# W5100_ethernet_shield.net
KiCad netlist of a schematic drawn in EAGLE
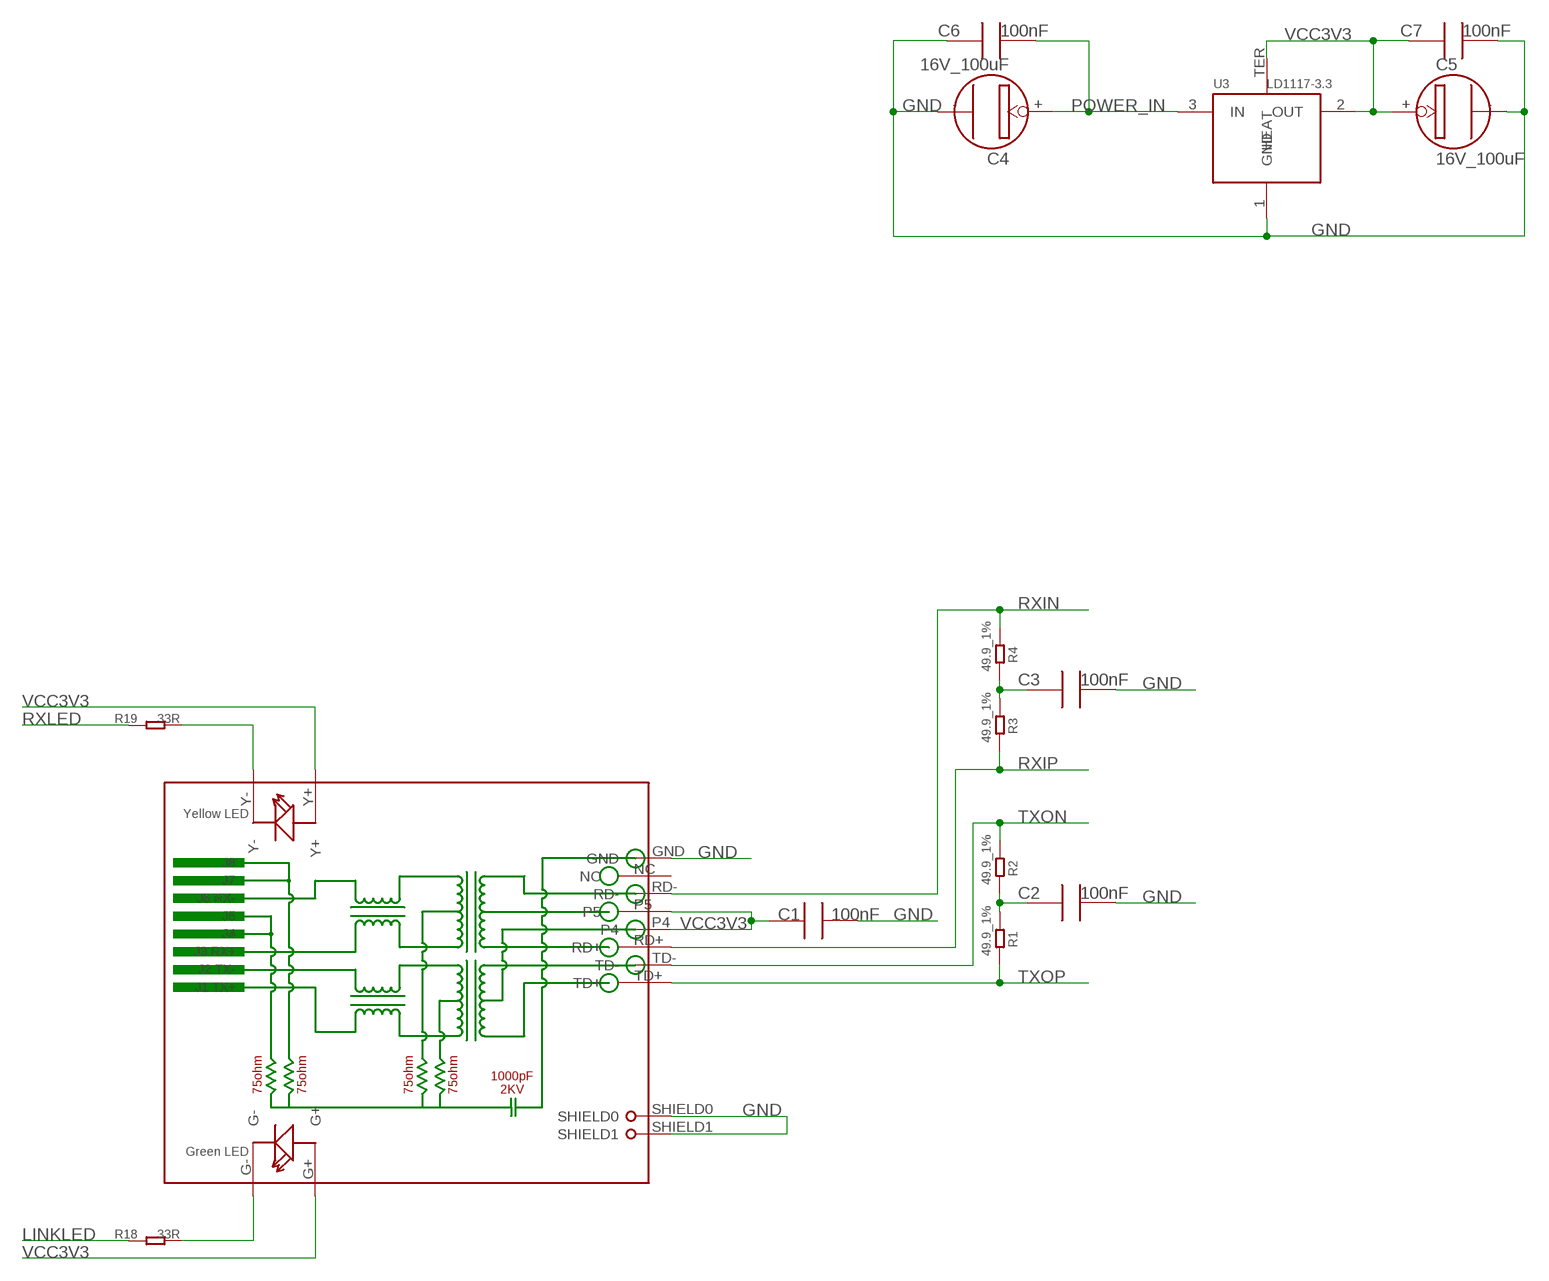
[diagram p0: schematic, sheet 1, part 1 of 2]
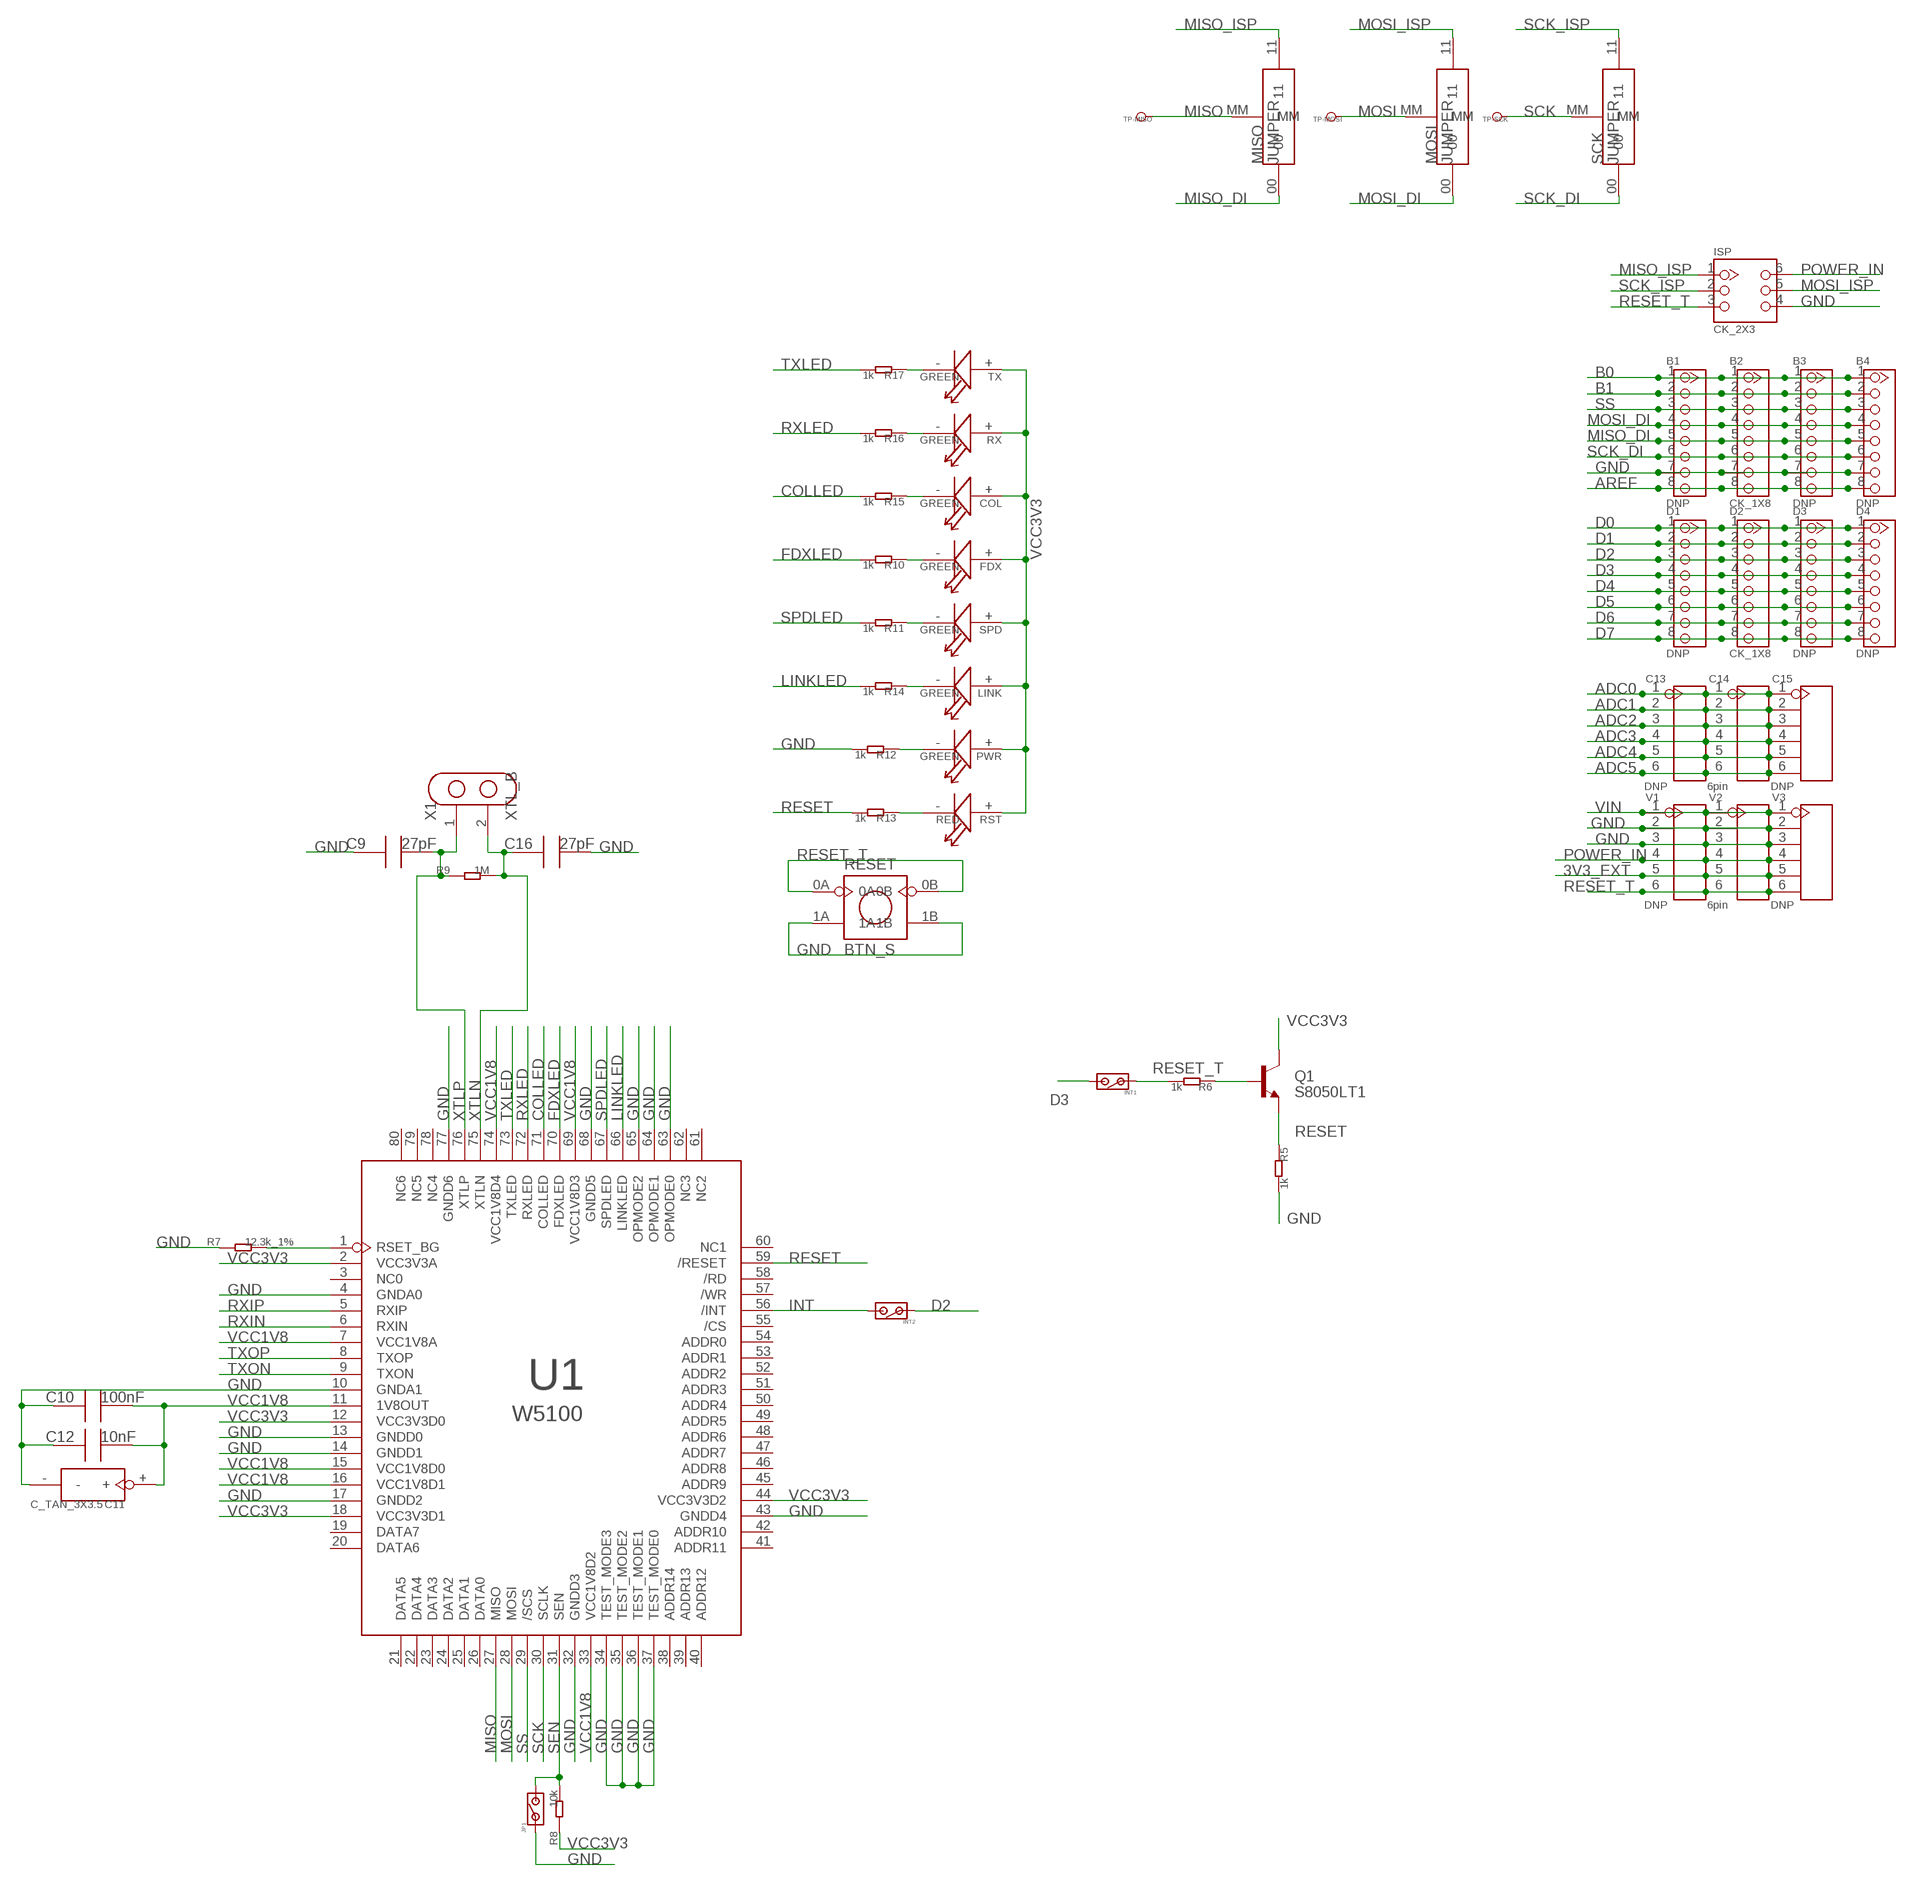
[diagram p1: schematic, sheet 1, part 2 of 2]

(export (version "E")
  (design (tool "Eeschema 10.0.6"))
  (components
    (comp (ref "B1")
      (value "DNP")
      (footprint "eagle-import:CK_1X8")
      (libsource (lib "eagle-import") (part "CK_1X8DD"))
    )
    (comp (ref "B2")
      (value "CK_1X8")
      (footprint "eagle-import:CK_1X8")
      (libsource (lib "eagle-import") (part "CK_1X8DD"))
    )
    (comp (ref "B3")
      (value "DNP")
      (footprint "eagle-import:CK_1X8")
      (libsource (lib "eagle-import") (part "CK_1X8DD"))
    )
    (comp (ref "B4")
      (value "DNP")
      (footprint "eagle-import:CK_1X8")
      (libsource (lib "eagle-import") (part "CK_1X8DD"))
    )
    (comp (ref "C1")
      (value "100nF")
      (footprint "eagle-import:0603")
      (libsource (lib "eagle-import") (part "C0603"))
    )
    (comp (ref "C2")
      (value "100nF")
      (footprint "eagle-import:0603")
      (libsource (lib "eagle-import") (part "C0603"))
    )
    (comp (ref "C3")
      (value "100nF")
      (footprint "eagle-import:0603")
      (libsource (lib "eagle-import") (part "C0603"))
    )
    (comp (ref "C4")
      (value "16V_100uF")
      (footprint "eagle-import:SANYO-OSCON_SMD_C6")
      (libsource (lib "eagle-import") (part "PANASONIC_D260"))
    )
    (comp (ref "C5")
      (value "16V_100uF")
      (footprint "eagle-import:SANYO-OSCON_SMD_C6")
      (libsource (lib "eagle-import") (part "PANASONIC_D260"))
    )
    (comp (ref "C6")
      (value "100nF")
      (footprint "eagle-import:0603")
      (libsource (lib "eagle-import") (part "C0603"))
    )
    (comp (ref "C7")
      (value "100nF")
      (footprint "eagle-import:0603")
      (libsource (lib "eagle-import") (part "C0603"))
    )
    (comp (ref "C9")
      (value "27pF")
      (footprint "eagle-import:0603")
      (libsource (lib "eagle-import") (part "C0603"))
    )
    (comp (ref "C10")
      (value "100nF")
      (footprint "eagle-import:0603")
      (libsource (lib "eagle-import") (part "C0603"))
    )
    (comp (ref "C11")
      (value "C_TAN_3X3.5")
      (footprint "eagle-import:C_TAN_3X3.5")
      (libsource (lib "eagle-import") (part "C_TAN_3X3.5"))
    )
    (comp (ref "C12")
      (value "10nF")
      (footprint "eagle-import:0603")
      (libsource (lib "eagle-import") (part "C0603"))
    )
    (comp (ref "C13")
      (value "DNP")
      (footprint "eagle-import:CK_1_6")
      (libsource (lib "eagle-import") (part "CK_16"))
    )
    (comp (ref "C14")
      (value "6pin")
      (footprint "eagle-import:CK_1_6")
      (libsource (lib "eagle-import") (part "CK_16"))
    )
    (comp (ref "C15")
      (value "DNP")
      (footprint "eagle-import:CK_1_6")
      (libsource (lib "eagle-import") (part "CK_16"))
    )
    (comp (ref "C16")
      (value "27pF")
      (footprint "eagle-import:0603")
      (libsource (lib "eagle-import") (part "C0603"))
    )
    (comp (ref "COL")
      (value "GREEN")
      (footprint "eagle-import:LED0805")
      (libsource (lib "eagle-import") (part "LED0805"))
    )
    (comp (ref "D1")
      (value "DNP")
      (footprint "eagle-import:CK_1X8")
      (libsource (lib "eagle-import") (part "CK_1X8DD"))
    )
    (comp (ref "D2")
      (value "CK_1X8")
      (footprint "eagle-import:CK_1X8")
      (libsource (lib "eagle-import") (part "CK_1X8DD"))
    )
    (comp (ref "D3")
      (value "DNP")
      (footprint "eagle-import:CK_1X8")
      (libsource (lib "eagle-import") (part "CK_1X8DD"))
    )
    (comp (ref "D4")
      (value "DNP")
      (footprint "eagle-import:CK_1X8")
      (libsource (lib "eagle-import") (part "CK_1X8DD"))
    )
    (comp (ref "FDX")
      (value "GREEN")
      (footprint "eagle-import:LED0805")
      (libsource (lib "eagle-import") (part "LED0805"))
    )
    (comp (ref "INT1")
      (value "DNP")
      (footprint "eagle-import:JP_SW")
      (libsource (lib "eagle-import") (part "JP_SW"))
    )
    (comp (ref "INT2")
      (value "DNP")
      (footprint "eagle-import:JP_SW")
      (libsource (lib "eagle-import") (part "JP_SW"))
    )
    (comp (ref "ISP")
      (value "CK_2X3")
      (footprint "eagle-import:CK_2X3_THIN")
      (libsource (lib "eagle-import") (part "CK_2X3"))
    )
    (comp (ref "JP1")
      (value "DNP")
      (footprint "eagle-import:JP_SW")
      (libsource (lib "eagle-import") (part "JP_SW"))
    )
    (comp (ref "LINK")
      (value "GREEN")
      (footprint "eagle-import:LED0805")
      (libsource (lib "eagle-import") (part "LED0805"))
    )
    (comp (ref "MISO")
      (value "JUMPER")
      (footprint "eagle-import:JUMPER")
      (libsource (lib "eagle-import") (part "JUMPER"))
    )
    (comp (ref "MOSI")
      (value "JUMPER")
      (footprint "eagle-import:JUMPER")
      (libsource (lib "eagle-import") (part "JUMPER"))
    )
    (comp (ref "PWR")
      (value "GREEN")
      (footprint "eagle-import:LED0805")
      (libsource (lib "eagle-import") (part "LED0805"))
    )
    (comp (ref "Q1")
      (value "S8050LT1")
      (footprint "eagle-import:SOT23")
      (libsource (lib "eagle-import") (part "TRANSISTOR_NPNSOT23"))
    )
    (comp (ref "R1")
      (value "49.9_1%")
      (footprint "eagle-import:0603")
      (libsource (lib "eagle-import") (part "R0603"))
    )
    (comp (ref "R2")
      (value "49.9_1%")
      (footprint "eagle-import:0603")
      (libsource (lib "eagle-import") (part "R0603"))
    )
    (comp (ref "R3")
      (value "49.9_1%")
      (footprint "eagle-import:0603")
      (libsource (lib "eagle-import") (part "R0603"))
    )
    (comp (ref "R4")
      (value "49.9_1%")
      (footprint "eagle-import:0603")
      (libsource (lib "eagle-import") (part "R0603"))
    )
    (comp (ref "R5")
      (value "1k")
      (footprint "eagle-import:0603")
      (libsource (lib "eagle-import") (part "R0603"))
    )
    (comp (ref "R6")
      (value "1k")
      (footprint "eagle-import:0603")
      (libsource (lib "eagle-import") (part "R0603"))
    )
    (comp (ref "R7")
      (value "12.3k_1%")
      (footprint "eagle-import:0603")
      (libsource (lib "eagle-import") (part "R0603"))
    )
    (comp (ref "R8")
      (value "10k")
      (footprint "eagle-import:0603")
      (libsource (lib "eagle-import") (part "R0603"))
    )
    (comp (ref "R9")
      (value "1M")
      (footprint "eagle-import:0603")
      (libsource (lib "eagle-import") (part "R0603"))
    )
    (comp (ref "R10")
      (value "1k")
      (footprint "eagle-import:0603")
      (libsource (lib "eagle-import") (part "R0603"))
    )
    (comp (ref "R11")
      (value "1k")
      (footprint "eagle-import:0603")
      (libsource (lib "eagle-import") (part "R0603"))
    )
    (comp (ref "R12")
      (value "1k")
      (footprint "eagle-import:0603")
      (libsource (lib "eagle-import") (part "R0603"))
    )
    (comp (ref "R13")
      (value "1k")
      (footprint "eagle-import:0603")
      (libsource (lib "eagle-import") (part "R0603"))
    )
    (comp (ref "R14")
      (value "1k")
      (footprint "eagle-import:0603")
      (libsource (lib "eagle-import") (part "R0603"))
    )
    (comp (ref "R15")
      (value "1k")
      (footprint "eagle-import:0603")
      (libsource (lib "eagle-import") (part "R0603"))
    )
    (comp (ref "R16")
      (value "1k")
      (footprint "eagle-import:0603")
      (libsource (lib "eagle-import") (part "R0603"))
    )
    (comp (ref "R17")
      (value "1k")
      (footprint "eagle-import:0603")
      (libsource (lib "eagle-import") (part "R0603"))
    )
    (comp (ref "R18")
      (value "33R")
      (footprint "eagle-import:0603")
      (libsource (lib "eagle-import") (part "R0603"))
    )
    (comp (ref "R19")
      (value "33R")
      (footprint "eagle-import:0603")
      (libsource (lib "eagle-import") (part "R0603"))
    )
    (comp (ref "RESET")
      (value "BTN_S")
      (footprint "eagle-import:BTN_S")
      (libsource (lib "eagle-import") (part "BTN_S"))
    )
    (comp (ref "RJ1")
      (value "HR911105A")
      (footprint "eagle-import:HR911105A")
      (libsource (lib "eagle-import") (part "HR911105A"))
    )
    (comp (ref "RST")
      (value "RED")
      (footprint "eagle-import:LED0805")
      (libsource (lib "eagle-import") (part "LED0805"))
    )
    (comp (ref "RX")
      (value "GREEN")
      (footprint "eagle-import:LED0805")
      (libsource (lib "eagle-import") (part "LED0805"))
    )
    (comp (ref "SCK")
      (value "JUMPER")
      (footprint "eagle-import:JUMPER")
      (libsource (lib "eagle-import") (part "JUMPER"))
    )
    (comp (ref "SPD")
      (value "GREEN")
      (footprint "eagle-import:LED0805")
      (libsource (lib "eagle-import") (part "LED0805"))
    )
    (comp (ref "TP-MISO")
      (value "DNP")
      (footprint "eagle-import:TP_45X45")
      (libsource (lib "eagle-import") (part "PAD-TEST-POINT-CIRCLE'45X45'"))
    )
    (comp (ref "TP-MOSI")
      (value "DNP")
      (footprint "eagle-import:TP_45X45")
      (libsource (lib "eagle-import") (part "PAD-TEST-POINT-CIRCLE'45X45'"))
    )
    (comp (ref "TP-SCK")
      (value "DNP")
      (footprint "eagle-import:TP_45X45")
      (libsource (lib "eagle-import") (part "PAD-TEST-POINT-CIRCLE'45X45'"))
    )
    (comp (ref "TX")
      (value "GREEN")
      (footprint "eagle-import:LED0805")
      (libsource (lib "eagle-import") (part "LED0805"))
    )
    (comp (ref "U1")
      (value "W5100")
      (footprint "eagle-import:SQFP80")
      (libsource (lib "eagle-import") (part "W5100"))
    )
    (comp (ref "U3")
      (value "LD1117-3.3")
      (footprint "eagle-import:SOT223")
      (libsource (lib "eagle-import") (part "LD1117SOT223"))
    )
    (comp (ref "V1")
      (value "DNP")
      (footprint "eagle-import:CK_1_6")
      (libsource (lib "eagle-import") (part "CK_16"))
    )
    (comp (ref "V2")
      (value "6pin")
      (footprint "eagle-import:CK_1_6")
      (libsource (lib "eagle-import") (part "CK_16"))
    )
    (comp (ref "V3")
      (value "DNP")
      (footprint "eagle-import:CK_1_6")
      (libsource (lib "eagle-import") (part "CK_16"))
    )
    (comp (ref "X1")
      (value "XTL_B")
      (footprint "eagle-import:XTL_B")
      (libsource (lib "eagle-import") (part "XTL_B"))
    )
  )
  (nets
    (net (code "1") (name "/3V3_EXT") (class "Default")
      (node (ref "V1") (pin "5") (pinfunction "5_5") (pintype "bidirectional"))
      (node (ref "V2") (pin "5") (pinfunction "5_5") (pintype "bidirectional"))
      (node (ref "V3") (pin "5") (pinfunction "5_5") (pintype "bidirectional"))
    )
    (net (code "2") (name "/ADC0") (class "Default")
      (node (ref "C13") (pin "1") (pinfunction "1_1") (pintype "bidirectional"))
      (node (ref "C14") (pin "1") (pinfunction "1_1") (pintype "bidirectional"))
      (node (ref "C15") (pin "1") (pinfunction "1_1") (pintype "bidirectional"))
    )
    (net (code "3") (name "/ADC1") (class "Default")
      (node (ref "C13") (pin "2") (pinfunction "2_2") (pintype "bidirectional"))
      (node (ref "C14") (pin "2") (pinfunction "2_2") (pintype "bidirectional"))
      (node (ref "C15") (pin "2") (pinfunction "2_2") (pintype "bidirectional"))
    )
    (net (code "4") (name "/ADC2") (class "Default")
      (node (ref "C13") (pin "3") (pinfunction "3_3") (pintype "bidirectional"))
      (node (ref "C14") (pin "3") (pinfunction "3_3") (pintype "bidirectional"))
      (node (ref "C15") (pin "3") (pinfunction "3_3") (pintype "bidirectional"))
    )
    (net (code "5") (name "/ADC3") (class "Default")
      (node (ref "C13") (pin "4") (pinfunction "4_4") (pintype "bidirectional"))
      (node (ref "C14") (pin "4") (pinfunction "4_4") (pintype "bidirectional"))
      (node (ref "C15") (pin "4") (pinfunction "4_4") (pintype "bidirectional"))
    )
    (net (code "6") (name "/ADC4") (class "Default")
      (node (ref "C13") (pin "5") (pinfunction "5_5") (pintype "bidirectional"))
      (node (ref "C14") (pin "5") (pinfunction "5_5") (pintype "bidirectional"))
      (node (ref "C15") (pin "5") (pinfunction "5_5") (pintype "bidirectional"))
    )
    (net (code "7") (name "/ADC5") (class "Default")
      (node (ref "C13") (pin "6") (pinfunction "6_6") (pintype "bidirectional"))
      (node (ref "C14") (pin "6") (pinfunction "6_6") (pintype "bidirectional"))
      (node (ref "C15") (pin "6") (pinfunction "6_6") (pintype "bidirectional"))
    )
    (net (code "8") (name "/AREF") (class "Default")
      (node (ref "B1") (pin "8") (pinfunction "P$8_8") (pintype "bidirectional"))
      (node (ref "B2") (pin "8") (pinfunction "P$8_8") (pintype "bidirectional"))
      (node (ref "B3") (pin "8") (pinfunction "P$8_8") (pintype "bidirectional"))
      (node (ref "B4") (pin "8") (pinfunction "P$8_8") (pintype "bidirectional"))
    )
    (net (code "9") (name "/B0") (class "Default")
      (node (ref "B1") (pin "1") (pinfunction "P$1_1") (pintype "bidirectional"))
      (node (ref "B2") (pin "1") (pinfunction "P$1_1") (pintype "bidirectional"))
      (node (ref "B3") (pin "1") (pinfunction "P$1_1") (pintype "bidirectional"))
      (node (ref "B4") (pin "1") (pinfunction "P$1_1") (pintype "bidirectional"))
    )
    (net (code "10") (name "/B1") (class "Default")
      (node (ref "B1") (pin "2") (pinfunction "P$2_2") (pintype "bidirectional"))
      (node (ref "B2") (pin "2") (pinfunction "P$2_2") (pintype "bidirectional"))
      (node (ref "B3") (pin "2") (pinfunction "P$2_2") (pintype "bidirectional"))
      (node (ref "B4") (pin "2") (pinfunction "P$2_2") (pintype "bidirectional"))
    )
    (net (code "11") (name "/COLLED") (class "Default")
      (node (ref "R15") (pin "2") (pinfunction "2_2") (pintype "bidirectional"))
      (node (ref "U1") (pin "71") (pinfunction "COLLED_71") (pintype "bidirectional"))
    )
    (net (code "12") (name "/D0") (class "Default")
      (node (ref "D1") (pin "1") (pinfunction "P$1_1") (pintype "bidirectional"))
      (node (ref "D2") (pin "1") (pinfunction "P$1_1") (pintype "bidirectional"))
      (node (ref "D3") (pin "1") (pinfunction "P$1_1") (pintype "bidirectional"))
      (node (ref "D4") (pin "1") (pinfunction "P$1_1") (pintype "bidirectional"))
    )
    (net (code "13") (name "/D1") (class "Default")
      (node (ref "D1") (pin "2") (pinfunction "P$2_2") (pintype "bidirectional"))
      (node (ref "D2") (pin "2") (pinfunction "P$2_2") (pintype "bidirectional"))
      (node (ref "D3") (pin "2") (pinfunction "P$2_2") (pintype "bidirectional"))
      (node (ref "D4") (pin "2") (pinfunction "P$2_2") (pintype "bidirectional"))
    )
    (net (code "14") (name "/D2") (class "Default")
      (node (ref "D1") (pin "3") (pinfunction "P$3_3") (pintype "bidirectional"))
      (node (ref "D2") (pin "3") (pinfunction "P$3_3") (pintype "bidirectional"))
      (node (ref "D3") (pin "3") (pinfunction "P$3_3") (pintype "bidirectional"))
      (node (ref "D4") (pin "3") (pinfunction "P$3_3") (pintype "bidirectional"))
      (node (ref "INT2") (pin "1") (pinfunction "1_1") (pintype "bidirectional"))
    )
    (net (code "15") (name "/D3") (class "Default")
      (node (ref "D1") (pin "4") (pinfunction "P$4_4") (pintype "bidirectional"))
      (node (ref "D2") (pin "4") (pinfunction "P$4_4") (pintype "bidirectional"))
      (node (ref "D3") (pin "4") (pinfunction "P$4_4") (pintype "bidirectional"))
      (node (ref "D4") (pin "4") (pinfunction "P$4_4") (pintype "bidirectional"))
      (node (ref "INT1") (pin "2") (pinfunction "2_2") (pintype "bidirectional"))
    )
    (net (code "16") (name "/D4") (class "Default")
      (node (ref "D1") (pin "5") (pinfunction "P$5_5") (pintype "bidirectional"))
      (node (ref "D2") (pin "5") (pinfunction "P$5_5") (pintype "bidirectional"))
      (node (ref "D3") (pin "5") (pinfunction "P$5_5") (pintype "bidirectional"))
      (node (ref "D4") (pin "5") (pinfunction "P$5_5") (pintype "bidirectional"))
    )
    (net (code "17") (name "/D5") (class "Default")
      (node (ref "D1") (pin "6") (pinfunction "P$6_6") (pintype "bidirectional"))
      (node (ref "D2") (pin "6") (pinfunction "P$6_6") (pintype "bidirectional"))
      (node (ref "D3") (pin "6") (pinfunction "P$6_6") (pintype "bidirectional"))
      (node (ref "D4") (pin "6") (pinfunction "P$6_6") (pintype "bidirectional"))
    )
    (net (code "18") (name "/D6") (class "Default")
      (node (ref "D1") (pin "7") (pinfunction "P$7_7") (pintype "bidirectional"))
      (node (ref "D2") (pin "7") (pinfunction "P$7_7") (pintype "bidirectional"))
      (node (ref "D3") (pin "7") (pinfunction "P$7_7") (pintype "bidirectional"))
      (node (ref "D4") (pin "7") (pinfunction "P$7_7") (pintype "bidirectional"))
    )
    (net (code "19") (name "/D7") (class "Default")
      (node (ref "D1") (pin "8") (pinfunction "P$8_8") (pintype "bidirectional"))
      (node (ref "D2") (pin "8") (pinfunction "P$8_8") (pintype "bidirectional"))
      (node (ref "D3") (pin "8") (pinfunction "P$8_8") (pintype "bidirectional"))
      (node (ref "D4") (pin "8") (pinfunction "P$8_8") (pintype "bidirectional"))
    )
    (net (code "20") (name "/FDXLED") (class "Default")
      (node (ref "R10") (pin "2") (pinfunction "2_2") (pintype "bidirectional"))
      (node (ref "U1") (pin "70") (pinfunction "FDXLED_70") (pintype "bidirectional"))
    )
    (net (code "21") (name "/GND") (class "Default")
      (node (ref "B1") (pin "7") (pinfunction "P$7_7") (pintype "bidirectional"))
      (node (ref "B2") (pin "7") (pinfunction "P$7_7") (pintype "bidirectional"))
      (node (ref "B3") (pin "7") (pinfunction "P$7_7") (pintype "bidirectional"))
      (node (ref "B4") (pin "7") (pinfunction "P$7_7") (pintype "bidirectional"))
      (node (ref "C1") (pin "2") (pinfunction "2_2") (pintype "bidirectional"))
      (node (ref "C10") (pin "1") (pinfunction "1_1") (pintype "bidirectional"))
      (node (ref "C11") (pin "-") (pinfunction "-_-") (pintype "bidirectional"))
      (node (ref "C12") (pin "1") (pinfunction "1_1") (pintype "bidirectional"))
      (node (ref "C16") (pin "2") (pinfunction "2_2") (pintype "bidirectional"))
      (node (ref "C2") (pin "2") (pinfunction "2_2") (pintype "bidirectional"))
      (node (ref "C3") (pin "2") (pinfunction "2_2") (pintype "bidirectional"))
      (node (ref "C4") (pin "-") (pinfunction "-_-") (pintype "bidirectional"))
      (node (ref "C5") (pin "-") (pinfunction "-_-") (pintype "bidirectional"))
      (node (ref "C6") (pin "1") (pinfunction "1_1") (pintype "bidirectional"))
      (node (ref "C7") (pin "2") (pinfunction "2_2") (pintype "bidirectional"))
      (node (ref "C9") (pin "1") (pinfunction "1_1") (pintype "bidirectional"))
      (node (ref "ISP") (pin "4") (pinfunction "P$4_4") (pintype "bidirectional"))
      (node (ref "JP1") (pin "1") (pinfunction "1_1") (pintype "bidirectional"))
      (node (ref "R12") (pin "2") (pinfunction "2_2") (pintype "bidirectional"))
      (node (ref "R5") (pin "2") (pinfunction "2_2") (pintype "bidirectional"))
      (node (ref "R7") (pin "1") (pinfunction "1_1") (pintype "bidirectional"))
      (node (ref "RESET") (pin "1A") (pinfunction "1A_1A") (pintype "bidirectional"))
      (node (ref "RESET") (pin "1B") (pinfunction "1B_1B") (pintype "bidirectional"))
      (node (ref "RJ1") (pin "GND") (pinfunction "GND_GND") (pintype "bidirectional"))
      (node (ref "RJ1") (pin "SHIELD0") (pinfunction "SHIELD0_SHIELD0") (pintype "bidirectional"))
      (node (ref "RJ1") (pin "SHIELD1") (pinfunction "SHIELD1_SHIELD1") (pintype "bidirectional"))
      (node (ref "U1") (pin "10") (pinfunction "GNDA1_10") (pintype "bidirectional"))
      (node (ref "U1") (pin "13") (pinfunction "GNDD0_13") (pintype "bidirectional"))
      (node (ref "U1") (pin "14") (pinfunction "GNDD1_14") (pintype "bidirectional"))
      (node (ref "U1") (pin "17") (pinfunction "GNDD2_17") (pintype "bidirectional"))
      (node (ref "U1") (pin "32") (pinfunction "GNDD3_32") (pintype "bidirectional"))
      (node (ref "U1") (pin "34") (pinfunction "TEST_MODE3_34") (pintype "bidirectional"))
      (node (ref "U1") (pin "35") (pinfunction "TEST_MODE2_35") (pintype "bidirectional"))
      (node (ref "U1") (pin "36") (pinfunction "TEST_MODE1_36") (pintype "bidirectional"))
      (node (ref "U1") (pin "37") (pinfunction "TEST_MODE0_37") (pintype "bidirectional"))
      (node (ref "U1") (pin "4") (pinfunction "GNDA0_4") (pintype "bidirectional"))
      (node (ref "U1") (pin "43") (pinfunction "GNDD4_43") (pintype "bidirectional"))
      (node (ref "U1") (pin "63") (pinfunction "OPMODE0_63") (pintype "bidirectional"))
      (node (ref "U1") (pin "64") (pinfunction "OPMODE1_64") (pintype "bidirectional"))
      (node (ref "U1") (pin "65") (pinfunction "OPMODE2_65") (pintype "bidirectional"))
      (node (ref "U1") (pin "68") (pinfunction "GNDD5_68") (pintype "bidirectional"))
      (node (ref "U1") (pin "77") (pinfunction "GNDD6_77") (pintype "bidirectional"))
      (node (ref "U3") (pin "1") (pinfunction "GND_1") (pintype "bidirectional"))
      (node (ref "V1") (pin "2") (pinfunction "2_2") (pintype "bidirectional"))
      (node (ref "V1") (pin "3") (pinfunction "3_3") (pintype "bidirectional"))
      (node (ref "V2") (pin "2") (pinfunction "2_2") (pintype "bidirectional"))
      (node (ref "V2") (pin "3") (pinfunction "3_3") (pintype "bidirectional"))
      (node (ref "V3") (pin "2") (pinfunction "2_2") (pintype "bidirectional"))
      (node (ref "V3") (pin "3") (pinfunction "3_3") (pintype "bidirectional"))
    )
    (net (code "22") (name "/INT") (class "Default")
      (node (ref "INT2") (pin "2") (pinfunction "2_2") (pintype "bidirectional"))
      (node (ref "U1") (pin "56") (pinfunction "/INT_56") (pintype "bidirectional"))
    )
    (net (code "23") (name "/LINKLED") (class "Default")
      (node (ref "R14") (pin "2") (pinfunction "2_2") (pintype "bidirectional"))
      (node (ref "R18") (pin "1") (pinfunction "1_1") (pintype "bidirectional"))
      (node (ref "U1") (pin "66") (pinfunction "LINKLED_66") (pintype "bidirectional"))
    )
    (net (code "24") (name "/MISO") (class "Default")
      (node (ref "MISO") (pin "MM") (pinfunction "MM_MM") (pintype "bidirectional"))
      (node (ref "TP-MISO") (pin "T") (pinfunction "T_T") (pintype "bidirectional"))
      (node (ref "U1") (pin "27") (pinfunction "MISO_27") (pintype "bidirectional"))
    )
    (net (code "25") (name "/MISO_DI") (class "Default")
      (node (ref "B1") (pin "5") (pinfunction "P$5_5") (pintype "bidirectional"))
      (node (ref "B2") (pin "5") (pinfunction "P$5_5") (pintype "bidirectional"))
      (node (ref "B3") (pin "5") (pinfunction "P$5_5") (pintype "bidirectional"))
      (node (ref "B4") (pin "5") (pinfunction "P$5_5") (pintype "bidirectional"))
      (node (ref "MISO") (pin "00") (pinfunction "00_00") (pintype "bidirectional"))
    )
    (net (code "26") (name "/MISO_ISP") (class "Default")
      (node (ref "ISP") (pin "1") (pinfunction "P$1_1") (pintype "bidirectional"))
      (node (ref "MISO") (pin "11") (pinfunction "11_11") (pintype "bidirectional"))
    )
    (net (code "27") (name "/MOSI") (class "Default")
      (node (ref "MOSI") (pin "MM") (pinfunction "MM_MM") (pintype "bidirectional"))
      (node (ref "TP-MOSI") (pin "T") (pinfunction "T_T") (pintype "bidirectional"))
      (node (ref "U1") (pin "28") (pinfunction "MOSI_28") (pintype "bidirectional"))
    )
    (net (code "28") (name "/MOSI_DI") (class "Default")
      (node (ref "B1") (pin "4") (pinfunction "P$4_4") (pintype "bidirectional"))
      (node (ref "B2") (pin "4") (pinfunction "P$4_4") (pintype "bidirectional"))
      (node (ref "B3") (pin "4") (pinfunction "P$4_4") (pintype "bidirectional"))
      (node (ref "B4") (pin "4") (pinfunction "P$4_4") (pintype "bidirectional"))
      (node (ref "MOSI") (pin "00") (pinfunction "00_00") (pintype "bidirectional"))
    )
    (net (code "29") (name "/MOSI_ISP") (class "Default")
      (node (ref "ISP") (pin "5") (pinfunction "P$5_5") (pintype "bidirectional"))
      (node (ref "MOSI") (pin "11") (pinfunction "11_11") (pintype "bidirectional"))
    )
    (net (code "30") (name "/POWER_IN") (class "Default")
      (node (ref "C4") (pin "+") (pinfunction "+_+") (pintype "bidirectional"))
      (node (ref "C6") (pin "2") (pinfunction "2_2") (pintype "bidirectional"))
      (node (ref "ISP") (pin "6") (pinfunction "P$6_6") (pintype "bidirectional"))
      (node (ref "U3") (pin "3") (pinfunction "IN_3") (pintype "bidirectional"))
      (node (ref "V1") (pin "4") (pinfunction "4_4") (pintype "bidirectional"))
      (node (ref "V2") (pin "4") (pinfunction "4_4") (pintype "bidirectional"))
      (node (ref "V3") (pin "4") (pinfunction "4_4") (pintype "bidirectional"))
    )
    (net (code "31") (name "/RESET") (class "Default")
      (node (ref "Q1") (pin "2") (pinfunction "E_2") (pintype "passive"))
      (node (ref "R13") (pin "2") (pinfunction "2_2") (pintype "bidirectional"))
      (node (ref "R5") (pin "1") (pinfunction "1_1") (pintype "bidirectional"))
      (node (ref "U1") (pin "59") (pinfunction "/RESET_59") (pintype "bidirectional"))
    )
    (net (code "32") (name "/RESET_T") (class "Default")
      (node (ref "INT1") (pin "1") (pinfunction "1_1") (pintype "bidirectional"))
      (node (ref "ISP") (pin "3") (pinfunction "P$3_3") (pintype "bidirectional"))
      (node (ref "R6") (pin "2") (pinfunction "2_2") (pintype "bidirectional"))
      (node (ref "RESET") (pin "0A") (pinfunction "0A_0A") (pintype "bidirectional"))
      (node (ref "RESET") (pin "0B") (pinfunction "0B_0B") (pintype "bidirectional"))
      (node (ref "V1") (pin "6") (pinfunction "6_6") (pintype "bidirectional"))
      (node (ref "V2") (pin "6") (pinfunction "6_6") (pintype "bidirectional"))
      (node (ref "V3") (pin "6") (pinfunction "6_6") (pintype "bidirectional"))
    )
    (net (code "33") (name "/RXIN") (class "Default")
      (node (ref "R4") (pin "1") (pinfunction "1_1") (pintype "bidirectional"))
      (node (ref "RJ1") (pin "RD-") (pinfunction "RD-_RD-") (pintype "bidirectional"))
      (node (ref "U1") (pin "6") (pinfunction "RXIN_6") (pintype "bidirectional"))
    )
    (net (code "34") (name "/RXIP") (class "Default")
      (node (ref "R3") (pin "2") (pinfunction "2_2") (pintype "bidirectional"))
      (node (ref "RJ1") (pin "RD+") (pinfunction "RD+_RD+") (pintype "bidirectional"))
      (node (ref "U1") (pin "5") (pinfunction "RXIP_5") (pintype "bidirectional"))
    )
    (net (code "35") (name "/RXLED") (class "Default")
      (node (ref "R16") (pin "2") (pinfunction "2_2") (pintype "bidirectional"))
      (node (ref "R19") (pin "1") (pinfunction "1_1") (pintype "bidirectional"))
      (node (ref "U1") (pin "72") (pinfunction "RXLED_72") (pintype "bidirectional"))
    )
    (net (code "36") (name "/SCK") (class "Default")
      (node (ref "SCK") (pin "MM") (pinfunction "MM_MM") (pintype "bidirectional"))
      (node (ref "TP-SCK") (pin "T") (pinfunction "T_T") (pintype "bidirectional"))
      (node (ref "U1") (pin "30") (pinfunction "SCLK_30") (pintype "bidirectional"))
    )
    (net (code "37") (name "/SCK_DI") (class "Default")
      (node (ref "B1") (pin "6") (pinfunction "P$6_6") (pintype "bidirectional"))
      (node (ref "B2") (pin "6") (pinfunction "P$6_6") (pintype "bidirectional"))
      (node (ref "B3") (pin "6") (pinfunction "P$6_6") (pintype "bidirectional"))
      (node (ref "B4") (pin "6") (pinfunction "P$6_6") (pintype "bidirectional"))
      (node (ref "SCK") (pin "00") (pinfunction "00_00") (pintype "bidirectional"))
    )
    (net (code "38") (name "/SCK_ISP") (class "Default")
      (node (ref "ISP") (pin "2") (pinfunction "P$2_2") (pintype "bidirectional"))
      (node (ref "SCK") (pin "11") (pinfunction "11_11") (pintype "bidirectional"))
    )
    (net (code "39") (name "/SEN") (class "Default")
      (node (ref "JP1") (pin "2") (pinfunction "2_2") (pintype "bidirectional"))
      (node (ref "R8") (pin "2") (pinfunction "2_2") (pintype "bidirectional"))
      (node (ref "U1") (pin "31") (pinfunction "SEN_31") (pintype "bidirectional"))
    )
    (net (code "40") (name "/SPDLED") (class "Default")
      (node (ref "R11") (pin "2") (pinfunction "2_2") (pintype "bidirectional"))
      (node (ref "U1") (pin "67") (pinfunction "SPDLED_67") (pintype "bidirectional"))
    )
    (net (code "41") (name "/SS") (class "Default")
      (node (ref "B1") (pin "3") (pinfunction "P$3_3") (pintype "bidirectional"))
      (node (ref "B2") (pin "3") (pinfunction "P$3_3") (pintype "bidirectional"))
      (node (ref "B3") (pin "3") (pinfunction "P$3_3") (pintype "bidirectional"))
      (node (ref "B4") (pin "3") (pinfunction "P$3_3") (pintype "bidirectional"))
      (node (ref "U1") (pin "29") (pinfunction "/SCS_29") (pintype "bidirectional"))
    )
    (net (code "42") (name "/TXLED") (class "Default")
      (node (ref "R17") (pin "2") (pinfunction "2_2") (pintype "bidirectional"))
      (node (ref "U1") (pin "73") (pinfunction "TXLED_73") (pintype "bidirectional"))
    )
    (net (code "43") (name "/TXON") (class "Default")
      (node (ref "R2") (pin "1") (pinfunction "1_1") (pintype "bidirectional"))
      (node (ref "RJ1") (pin "TD-") (pinfunction "TD-_TD-") (pintype "bidirectional"))
      (node (ref "U1") (pin "9") (pinfunction "TXON_9") (pintype "bidirectional"))
    )
    (net (code "44") (name "/TXOP") (class "Default")
      (node (ref "R1") (pin "2") (pinfunction "2_2") (pintype "bidirectional"))
      (node (ref "RJ1") (pin "TD+") (pinfunction "TD+_TD+") (pintype "bidirectional"))
      (node (ref "U1") (pin "8") (pinfunction "TXOP_8") (pintype "bidirectional"))
    )
    (net (code "45") (name "/VCC1V8") (class "Default")
      (node (ref "C10") (pin "2") (pinfunction "2_2") (pintype "bidirectional"))
      (node (ref "C11") (pin "+") (pinfunction "+_+") (pintype "bidirectional"))
      (node (ref "C12") (pin "2") (pinfunction "2_2") (pintype "bidirectional"))
      (node (ref "U1") (pin "11") (pinfunction "1V8OUT_11") (pintype "bidirectional"))
      (node (ref "U1") (pin "15") (pinfunction "VCC1V8D0_15") (pintype "bidirectional"))
      (node (ref "U1") (pin "16") (pinfunction "VCC1V8D1_16") (pintype "bidirectional"))
      (node (ref "U1") (pin "33") (pinfunction "VCC1V8D2_33") (pintype "bidirectional"))
      (node (ref "U1") (pin "69") (pinfunction "VCC1V8D3_69") (pintype "bidirectional"))
      (node (ref "U1") (pin "7") (pinfunction "VCC1V8A_7") (pintype "bidirectional"))
      (node (ref "U1") (pin "74") (pinfunction "VCC1V8D4_74") (pintype "bidirectional"))
    )
    (net (code "46") (name "/VCC3V3") (class "Default")
      (node (ref "C1") (pin "1") (pinfunction "1_1") (pintype "bidirectional"))
      (node (ref "C5") (pin "+") (pinfunction "+_+") (pintype "bidirectional"))
      (node (ref "C7") (pin "1") (pinfunction "1_1") (pintype "bidirectional"))
      (node (ref "COL") (pin "+") (pinfunction "+_+") (pintype "bidirectional"))
      (node (ref "FDX") (pin "+") (pinfunction "+_+") (pintype "bidirectional"))
      (node (ref "LINK") (pin "+") (pinfunction "+_+") (pintype "bidirectional"))
      (node (ref "PWR") (pin "+") (pinfunction "+_+") (pintype "bidirectional"))
      (node (ref "Q1") (pin "3") (pinfunction "C_3") (pintype "passive"))
      (node (ref "R8") (pin "1") (pinfunction "1_1") (pintype "bidirectional"))
      (node (ref "RJ1") (pin "G+") (pinfunction "G+_G+") (pintype "bidirectional"))
      (node (ref "RJ1") (pin "P4") (pinfunction "P4_P4") (pintype "bidirectional"))
      (node (ref "RJ1") (pin "P5") (pinfunction "P5_P5") (pintype "bidirectional"))
      (node (ref "RJ1") (pin "Y+") (pinfunction "Y+_Y+") (pintype "bidirectional"))
      (node (ref "RST") (pin "+") (pinfunction "+_+") (pintype "bidirectional"))
      (node (ref "RX") (pin "+") (pinfunction "+_+") (pintype "bidirectional"))
      (node (ref "SPD") (pin "+") (pinfunction "+_+") (pintype "bidirectional"))
      (node (ref "TX") (pin "+") (pinfunction "+_+") (pintype "bidirectional"))
      (node (ref "U1") (pin "12") (pinfunction "VCC3V3D0_12") (pintype "bidirectional"))
      (node (ref "U1") (pin "18") (pinfunction "VCC3V3D1_18") (pintype "bidirectional"))
      (node (ref "U1") (pin "2") (pinfunction "VCC3V3A_2") (pintype "bidirectional"))
      (node (ref "U1") (pin "44") (pinfunction "VCC3V3D2_44") (pintype "bidirectional"))
      (node (ref "U3") (pin "2") (pinfunction "OUT_2") (pintype "bidirectional"))
      (node (ref "U3") (pin "TER") (pinfunction "HEAT_TER") (pintype "bidirectional"))
    )
    (net (code "47") (name "/VIN") (class "Default")
      (node (ref "V1") (pin "1") (pinfunction "1_1") (pintype "bidirectional"))
      (node (ref "V2") (pin "1") (pinfunction "1_1") (pintype "bidirectional"))
      (node (ref "V3") (pin "1") (pinfunction "1_1") (pintype "bidirectional"))
    )
    (net (code "48") (name "/XTLN") (class "Default")
      (node (ref "C16") (pin "1") (pinfunction "1_1") (pintype "bidirectional"))
      (node (ref "R9") (pin "2") (pinfunction "2_2") (pintype "bidirectional"))
      (node (ref "U1") (pin "75") (pinfunction "XTLN_75") (pintype "bidirectional"))
      (node (ref "X1") (pin "2") (pinfunction "P$2_2") (pintype "bidirectional"))
    )
    (net (code "49") (name "/XTLP") (class "Default")
      (node (ref "C9") (pin "2") (pinfunction "2_2") (pintype "bidirectional"))
      (node (ref "R9") (pin "1") (pinfunction "1_1") (pintype "bidirectional"))
      (node (ref "U1") (pin "76") (pinfunction "XTLP_76") (pintype "bidirectional"))
      (node (ref "X1") (pin "1") (pinfunction "P$1_1") (pintype "bidirectional"))
    )
    (net (code "50") (name "Net-(C2-Pad1)") (class "Default")
      (node (ref "C2") (pin "1") (pinfunction "1_1") (pintype "bidirectional"))
      (node (ref "R1") (pin "1") (pinfunction "1_1") (pintype "bidirectional"))
      (node (ref "R2") (pin "2") (pinfunction "2_2") (pintype "bidirectional"))
    )
    (net (code "51") (name "Net-(C3-Pad1)") (class "Default")
      (node (ref "C3") (pin "1") (pinfunction "1_1") (pintype "bidirectional"))
      (node (ref "R3") (pin "1") (pinfunction "1_1") (pintype "bidirectional"))
      (node (ref "R4") (pin "2") (pinfunction "2_2") (pintype "bidirectional"))
    )
    (net (code "52") (name "Net-(COL-Pad-)") (class "Default")
      (node (ref "COL") (pin "-") (pinfunction "-_-") (pintype "bidirectional"))
      (node (ref "R15") (pin "1") (pinfunction "1_1") (pintype "bidirectional"))
    )
    (net (code "53") (name "Net-(FDX-Pad-)") (class "Default")
      (node (ref "FDX") (pin "-") (pinfunction "-_-") (pintype "bidirectional"))
      (node (ref "R10") (pin "1") (pinfunction "1_1") (pintype "bidirectional"))
    )
    (net (code "54") (name "Net-(LINK-Pad-)") (class "Default")
      (node (ref "LINK") (pin "-") (pinfunction "-_-") (pintype "bidirectional"))
      (node (ref "R14") (pin "1") (pinfunction "1_1") (pintype "bidirectional"))
    )
    (net (code "55") (name "Net-(PWR-Pad-)") (class "Default")
      (node (ref "PWR") (pin "-") (pinfunction "-_-") (pintype "bidirectional"))
      (node (ref "R12") (pin "1") (pinfunction "1_1") (pintype "bidirectional"))
    )
    (net (code "56") (name "Net-(Q1-B)") (class "Default")
      (node (ref "Q1") (pin "1") (pinfunction "B_1") (pintype "passive"))
      (node (ref "R6") (pin "1") (pinfunction "1_1") (pintype "bidirectional"))
    )
    (net (code "57") (name "Net-(R11-Pad1)") (class "Default")
      (node (ref "R11") (pin "1") (pinfunction "1_1") (pintype "bidirectional"))
      (node (ref "SPD") (pin "-") (pinfunction "-_-") (pintype "bidirectional"))
    )
    (net (code "58") (name "Net-(R13-Pad1)") (class "Default")
      (node (ref "R13") (pin "1") (pinfunction "1_1") (pintype "bidirectional"))
      (node (ref "RST") (pin "-") (pinfunction "-_-") (pintype "bidirectional"))
    )
    (net (code "59") (name "Net-(R16-Pad1)") (class "Default")
      (node (ref "R16") (pin "1") (pinfunction "1_1") (pintype "bidirectional"))
      (node (ref "RX") (pin "-") (pinfunction "-_-") (pintype "bidirectional"))
    )
    (net (code "60") (name "Net-(R17-Pad1)") (class "Default")
      (node (ref "R17") (pin "1") (pinfunction "1_1") (pintype "bidirectional"))
      (node (ref "TX") (pin "-") (pinfunction "-_-") (pintype "bidirectional"))
    )
    (net (code "61") (name "Net-(R18-Pad2)") (class "Default")
      (node (ref "R18") (pin "2") (pinfunction "2_2") (pintype "bidirectional"))
      (node (ref "RJ1") (pin "G-") (pinfunction "G-_G-") (pintype "bidirectional"))
    )
    (net (code "62") (name "Net-(R19-Pad2)") (class "Default")
      (node (ref "R19") (pin "2") (pinfunction "2_2") (pintype "bidirectional"))
      (node (ref "RJ1") (pin "Y-") (pinfunction "Y-_Y-") (pintype "bidirectional"))
    )
    (net (code "63") (name "Net-(U1-RSET_BG)") (class "Default")
      (node (ref "R7") (pin "2") (pinfunction "2_2") (pintype "bidirectional"))
      (node (ref "U1") (pin "1") (pinfunction "RSET_BG_1") (pintype "bidirectional"))
    )
    (net (code "64") (name "unconnected-(RJ1-PadNC)") (class "Default")
      (node (ref "RJ1") (pin "NC") (pinfunction "NC_NC") (pintype "bidirectional"))
    )
    (net (code "65") (name "unconnected-(U1-ADDR0-Pad54)") (class "Default")
      (node (ref "U1") (pin "54") (pinfunction "ADDR0_54") (pintype "bidirectional"))
    )
    (net (code "66") (name "unconnected-(U1-ADDR1-Pad53)") (class "Default")
      (node (ref "U1") (pin "53") (pinfunction "ADDR1_53") (pintype "bidirectional"))
    )
    (net (code "67") (name "unconnected-(U1-ADDR2-Pad52)") (class "Default")
      (node (ref "U1") (pin "52") (pinfunction "ADDR2_52") (pintype "bidirectional"))
    )
    (net (code "68") (name "unconnected-(U1-ADDR3-Pad51)") (class "Default")
      (node (ref "U1") (pin "51") (pinfunction "ADDR3_51") (pintype "bidirectional"))
    )
    (net (code "69") (name "unconnected-(U1-ADDR4-Pad50)") (class "Default")
      (node (ref "U1") (pin "50") (pinfunction "ADDR4_50") (pintype "bidirectional"))
    )
    (net (code "70") (name "unconnected-(U1-ADDR5-Pad49)") (class "Default")
      (node (ref "U1") (pin "49") (pinfunction "ADDR5_49") (pintype "bidirectional"))
    )
    (net (code "71") (name "unconnected-(U1-ADDR6-Pad48)") (class "Default")
      (node (ref "U1") (pin "48") (pinfunction "ADDR6_48") (pintype "bidirectional"))
    )
    (net (code "72") (name "unconnected-(U1-ADDR7-Pad47)") (class "Default")
      (node (ref "U1") (pin "47") (pinfunction "ADDR7_47") (pintype "bidirectional"))
    )
    (net (code "73") (name "unconnected-(U1-ADDR8-Pad46)") (class "Default")
      (node (ref "U1") (pin "46") (pinfunction "ADDR8_46") (pintype "bidirectional"))
    )
    (net (code "74") (name "unconnected-(U1-ADDR9-Pad45)") (class "Default")
      (node (ref "U1") (pin "45") (pinfunction "ADDR9_45") (pintype "bidirectional"))
    )
    (net (code "75") (name "unconnected-(U1-ADDR10-Pad42)") (class "Default")
      (node (ref "U1") (pin "42") (pinfunction "ADDR10_42") (pintype "bidirectional"))
    )
    (net (code "76") (name "unconnected-(U1-ADDR11-Pad41)") (class "Default")
      (node (ref "U1") (pin "41") (pinfunction "ADDR11_41") (pintype "bidirectional"))
    )
    (net (code "77") (name "unconnected-(U1-ADDR12-Pad40)") (class "Default")
      (node (ref "U1") (pin "40") (pinfunction "ADDR12_40") (pintype "bidirectional"))
    )
    (net (code "78") (name "unconnected-(U1-ADDR13-Pad39)") (class "Default")
      (node (ref "U1") (pin "39") (pinfunction "ADDR13_39") (pintype "bidirectional"))
    )
    (net (code "79") (name "unconnected-(U1-ADDR14-Pad38)") (class "Default")
      (node (ref "U1") (pin "38") (pinfunction "ADDR14_38") (pintype "bidirectional"))
    )
    (net (code "80") (name "unconnected-(U1-DATA0-Pad26)") (class "Default")
      (node (ref "U1") (pin "26") (pinfunction "DATA0_26") (pintype "bidirectional"))
    )
    (net (code "81") (name "unconnected-(U1-DATA1-Pad25)") (class "Default")
      (node (ref "U1") (pin "25") (pinfunction "DATA1_25") (pintype "bidirectional"))
    )
    (net (code "82") (name "unconnected-(U1-DATA2-Pad24)") (class "Default")
      (node (ref "U1") (pin "24") (pinfunction "DATA2_24") (pintype "bidirectional"))
    )
    (net (code "83") (name "unconnected-(U1-DATA3-Pad23)") (class "Default")
      (node (ref "U1") (pin "23") (pinfunction "DATA3_23") (pintype "bidirectional"))
    )
    (net (code "84") (name "unconnected-(U1-DATA4-Pad22)") (class "Default")
      (node (ref "U1") (pin "22") (pinfunction "DATA4_22") (pintype "bidirectional"))
    )
    (net (code "85") (name "unconnected-(U1-DATA5-Pad21)") (class "Default")
      (node (ref "U1") (pin "21") (pinfunction "DATA5_21") (pintype "bidirectional"))
    )
    (net (code "86") (name "unconnected-(U1-DATA6-Pad20)") (class "Default")
      (node (ref "U1") (pin "20") (pinfunction "DATA6_20") (pintype "bidirectional"))
    )
    (net (code "87") (name "unconnected-(U1-DATA7-Pad19)") (class "Default")
      (node (ref "U1") (pin "19") (pinfunction "DATA7_19") (pintype "bidirectional"))
    )
    (net (code "88") (name "unconnected-(U1-NC0-Pad3)") (class "Default")
      (node (ref "U1") (pin "3") (pinfunction "NC0_3") (pintype "bidirectional"))
    )
    (net (code "89") (name "unconnected-(U1-NC1-Pad60)") (class "Default")
      (node (ref "U1") (pin "60") (pinfunction "NC1_60") (pintype "bidirectional"))
    )
    (net (code "90") (name "unconnected-(U1-NC2-Pad61)") (class "Default")
      (node (ref "U1") (pin "61") (pinfunction "NC2_61") (pintype "bidirectional"))
    )
    (net (code "91") (name "unconnected-(U1-NC3-Pad62)") (class "Default")
      (node (ref "U1") (pin "62") (pinfunction "NC3_62") (pintype "bidirectional"))
    )
    (net (code "92") (name "unconnected-(U1-NC4-Pad78)") (class "Default")
      (node (ref "U1") (pin "78") (pinfunction "NC4_78") (pintype "bidirectional"))
    )
    (net (code "93") (name "unconnected-(U1-NC5-Pad79)") (class "Default")
      (node (ref "U1") (pin "79") (pinfunction "NC5_79") (pintype "bidirectional"))
    )
    (net (code "94") (name "unconnected-(U1-NC6-Pad80)") (class "Default")
      (node (ref "U1") (pin "80") (pinfunction "NC6_80") (pintype "bidirectional"))
    )
    (net (code "95") (name "unconnected-(U1-{slash}CS-Pad55)") (class "Default")
      (node (ref "U1") (pin "55") (pinfunction "/CS_55") (pintype "bidirectional"))
    )
    (net (code "96") (name "unconnected-(U1-{slash}RD-Pad58)") (class "Default")
      (node (ref "U1") (pin "58") (pinfunction "/RD_58") (pintype "bidirectional"))
    )
    (net (code "97") (name "unconnected-(U1-{slash}WR-Pad57)") (class "Default")
      (node (ref "U1") (pin "57") (pinfunction "/WR_57") (pintype "bidirectional"))
    )
  )
)
